# MYO_power_distribution_pcb.net
KiCad netlist of a schematic drawn in EAGLE
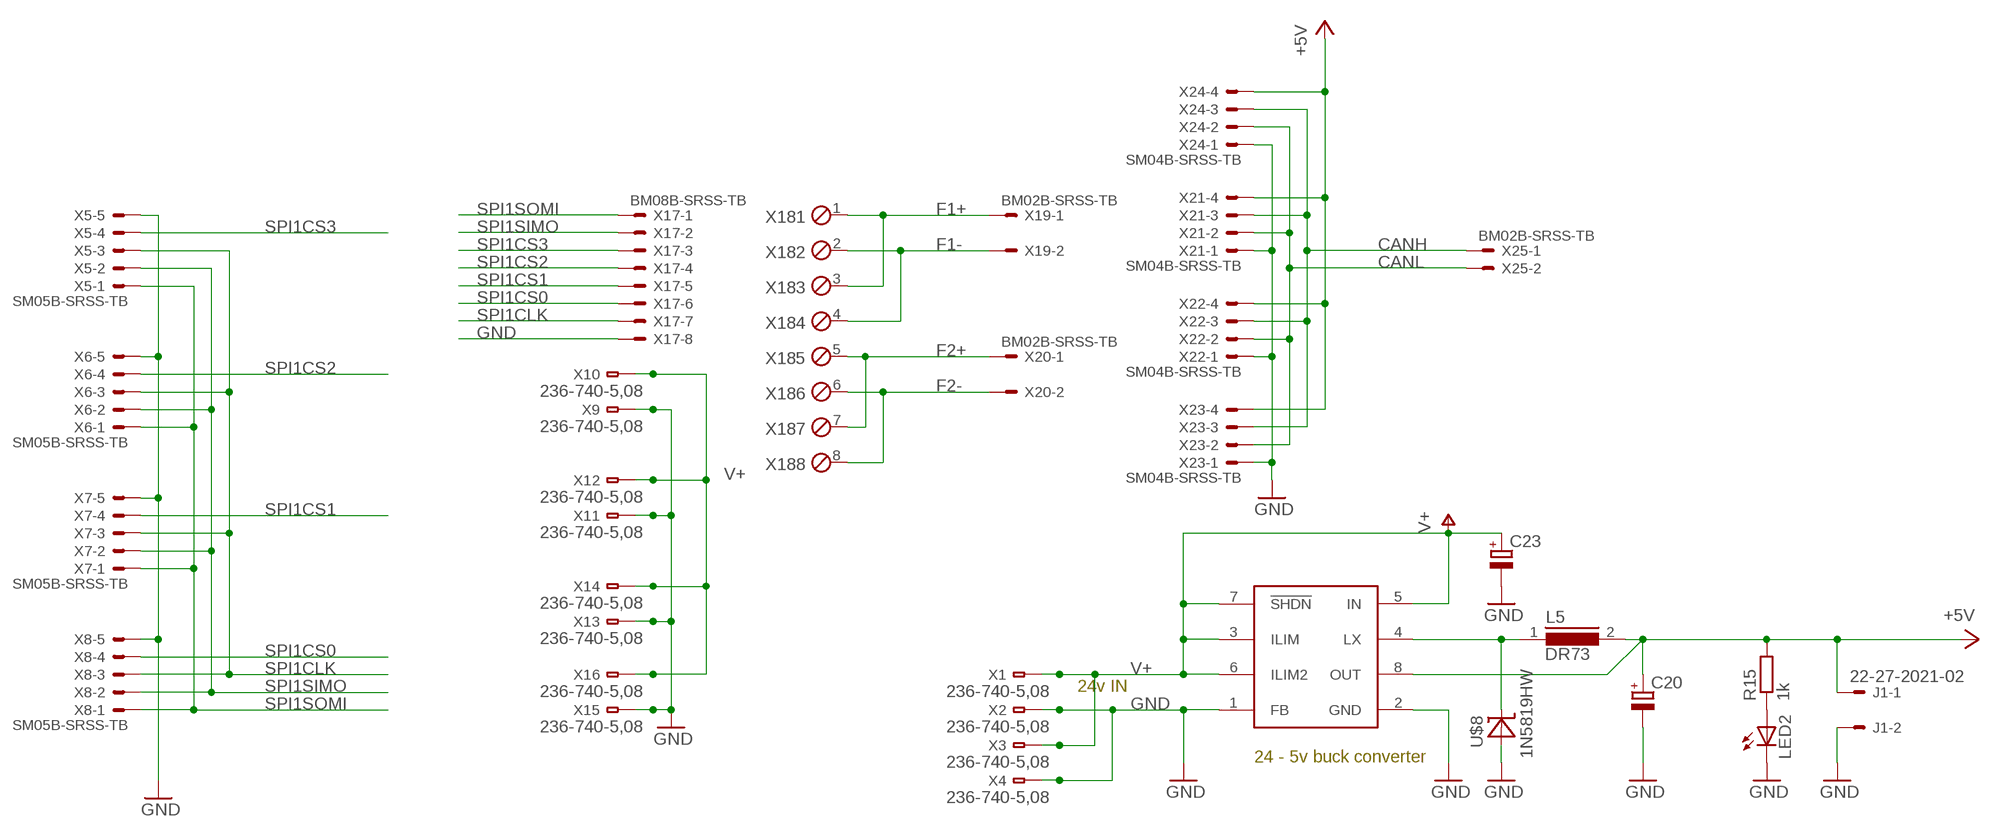
[diagram p0: schematic, sheet 1]

(export (version "E")
  (design (tool "Eeschema 10.0.6"))
  (components
    (comp (ref "C20")
      (value "CPOL-EUC/6032-28R")
      (footprint "eagle-import:C_6032-28R")
      (libsource (lib "eagle-import") (part "CPOL-EUC/6032-28R"))
    )
    (comp (ref "C23")
      (value "CPOL-EUC/6032-28R")
      (footprint "eagle-import:C_6032-28R")
      (libsource (lib "eagle-import") (part "CPOL-EUC/6032-28R"))
    )
    (comp (ref "J1")
      (value "22-27-2021-02")
      (footprint "eagle-import:6410-02")
      (libsource (lib "eagle-import") (part "22-?-0227-2021"))
    )
    (comp (ref "L5")
      (value "DR73")
      (footprint "eagle-import:DR73")
      (libsource (lib "eagle-import") (part "DR73"))
    )
    (comp (ref "LED2")
      (value "LEDCHIP-LED0805")
      (footprint "eagle-import:CHIP-LED0805")
      (libsource (lib "eagle-import") (part "LEDCHIP-LED0805"))
    )
    (comp (ref "R15")
      (value "1k")
      (footprint "eagle-import:R0603")
      (libsource (lib "eagle-import") (part "R-EU_R0603"))
    )
    (comp (ref "U$5")
      (value "MAX1776")
      (footprint "eagle-import:UMAX8")
      (libsource (lib "eagle-import") (part "MAX1776"))
    )
    (comp (ref "U$8")
      (value "1N5819HW")
      (footprint "eagle-import:SOD123")
      (libsource (lib "eagle-import") (part "1N5819HW"))
    )
    (comp (ref "X1")
      (value "236-740-5,08")
      (footprint "eagle-import:236-4XX")
      (libsource (lib "eagle-import") (part "236-5,08-740"))
    )
    (comp (ref "X2")
      (value "236-740-5,08")
      (footprint "eagle-import:236-4XX")
      (libsource (lib "eagle-import") (part "236-5,08-740"))
    )
    (comp (ref "X3")
      (value "236-740-5,08")
      (footprint "eagle-import:236-4XX")
      (libsource (lib "eagle-import") (part "236-5,08-740"))
    )
    (comp (ref "X4")
      (value "236-740-5,08")
      (footprint "eagle-import:236-4XX")
      (libsource (lib "eagle-import") (part "236-5,08-740"))
    )
    (comp (ref "X5")
      (value "SM05B-SRSS-TB")
      (footprint "eagle-import:SM05B-SRSS-TB")
      (libsource (lib "eagle-import") (part "?M05B-SRSS-TBS"))
    )
    (comp (ref "X6")
      (value "SM05B-SRSS-TB")
      (footprint "eagle-import:SM05B-SRSS-TB")
      (libsource (lib "eagle-import") (part "?M05B-SRSS-TBS"))
    )
    (comp (ref "X7")
      (value "SM05B-SRSS-TB")
      (footprint "eagle-import:SM05B-SRSS-TB")
      (libsource (lib "eagle-import") (part "?M05B-SRSS-TBS"))
    )
    (comp (ref "X8")
      (value "SM05B-SRSS-TB")
      (footprint "eagle-import:SM05B-SRSS-TB")
      (libsource (lib "eagle-import") (part "?M05B-SRSS-TBS"))
    )
    (comp (ref "X9")
      (value "236-740-5,08")
      (footprint "eagle-import:236-4XX")
      (libsource (lib "eagle-import") (part "236-5,08-740"))
    )
    (comp (ref "X10")
      (value "236-740-5,08")
      (footprint "eagle-import:236-4XX")
      (libsource (lib "eagle-import") (part "236-5,08-740"))
    )
    (comp (ref "X11")
      (value "236-740-5,08")
      (footprint "eagle-import:236-4XX")
      (libsource (lib "eagle-import") (part "236-5,08-740"))
    )
    (comp (ref "X12")
      (value "236-740-5,08")
      (footprint "eagle-import:236-4XX")
      (libsource (lib "eagle-import") (part "236-5,08-740"))
    )
    (comp (ref "X13")
      (value "236-740-5,08")
      (footprint "eagle-import:236-4XX")
      (libsource (lib "eagle-import") (part "236-5,08-740"))
    )
    (comp (ref "X14")
      (value "236-740-5,08")
      (footprint "eagle-import:236-4XX")
      (libsource (lib "eagle-import") (part "236-5,08-740"))
    )
    (comp (ref "X15")
      (value "236-740-5,08")
      (footprint "eagle-import:236-4XX")
      (libsource (lib "eagle-import") (part "236-5,08-740"))
    )
    (comp (ref "X16")
      (value "236-740-5,08")
      (footprint "eagle-import:236-4XX")
      (libsource (lib "eagle-import") (part "236-5,08-740"))
    )
    (comp (ref "X17")
      (value "BM08B-SRSS-TB")
      (footprint "eagle-import:BM08B-SRSS-TB")
      (libsource (lib "eagle-import") (part "?M08B-SRSS-TBB"))
    )
    (comp (ref "X18")
      (value "CON_PTSA_8")
      (footprint "eagle-import:PHOENIX_PSTA_8")
      (libsource (lib "eagle-import") (part "CON_PTSA_8"))
    )
    (comp (ref "X19")
      (value "BM02B-SRSS-TB")
      (footprint "eagle-import:BM02B-SRSS-TB")
      (libsource (lib "eagle-import") (part "?M02B-SRSS-TBB"))
    )
    (comp (ref "X20")
      (value "BM02B-SRSS-TB")
      (footprint "eagle-import:BM02B-SRSS-TB")
      (libsource (lib "eagle-import") (part "?M02B-SRSS-TBB"))
    )
    (comp (ref "X21")
      (value "SM04B-SRSS-TB")
      (footprint "eagle-import:SM04B-SRSS-TB")
      (libsource (lib "eagle-import") (part "?M04B-SRSS-TBS"))
    )
    (comp (ref "X22")
      (value "SM04B-SRSS-TB")
      (footprint "eagle-import:SM04B-SRSS-TB")
      (libsource (lib "eagle-import") (part "?M04B-SRSS-TBS"))
    )
    (comp (ref "X23")
      (value "SM04B-SRSS-TB")
      (footprint "eagle-import:SM04B-SRSS-TB")
      (libsource (lib "eagle-import") (part "?M04B-SRSS-TBS"))
    )
    (comp (ref "X24")
      (value "SM04B-SRSS-TB")
      (footprint "eagle-import:SM04B-SRSS-TB")
      (libsource (lib "eagle-import") (part "?M04B-SRSS-TBS"))
    )
    (comp (ref "X25")
      (value "BM02B-SRSS-TB")
      (footprint "eagle-import:BM02B-SRSS-TB")
      (libsource (lib "eagle-import") (part "?M02B-SRSS-TBB"))
    )
  )
  (nets
    (net (code "1") (name "+5V") (class "Default")
      (node (ref "C20") (pin "+") (pinfunction "+_+") (pintype "passive"))
      (node (ref "J1") (pin "1") (pinfunction "S_1") (pintype "passive"))
      (node (ref "L5") (pin "2") (pinfunction "2_2") (pintype "passive"))
      (node (ref "R15") (pin "2") (pinfunction "2_2") (pintype "passive"))
      (node (ref "U$5") (pin "8") (pinfunction "OUT_8") (pintype "bidirectional"))
      (node (ref "X21") (pin "4") (pinfunction "S_4") (pintype "passive"))
      (node (ref "X22") (pin "4") (pinfunction "S_4") (pintype "passive"))
      (node (ref "X23") (pin "4") (pinfunction "S_4") (pintype "passive"))
      (node (ref "X24") (pin "4") (pinfunction "S_4") (pintype "passive"))
    )
    (net (code "2") (name "/CANH") (class "Default")
      (node (ref "X21") (pin "3") (pinfunction "S_3") (pintype "passive"))
      (node (ref "X22") (pin "3") (pinfunction "S_3") (pintype "passive"))
      (node (ref "X23") (pin "3") (pinfunction "S_3") (pintype "passive"))
      (node (ref "X24") (pin "3") (pinfunction "S_3") (pintype "passive"))
      (node (ref "X25") (pin "1") (pinfunction "S_1") (pintype "passive"))
    )
    (net (code "3") (name "/CANL") (class "Default")
      (node (ref "X21") (pin "2") (pinfunction "S_2") (pintype "passive"))
      (node (ref "X22") (pin "2") (pinfunction "S_2") (pintype "passive"))
      (node (ref "X23") (pin "2") (pinfunction "S_2") (pintype "passive"))
      (node (ref "X24") (pin "2") (pinfunction "S_2") (pintype "passive"))
      (node (ref "X25") (pin "2") (pinfunction "S_2") (pintype "passive"))
    )
    (net (code "4") (name "/F1+") (class "Default")
      (node (ref "X18") (pin "1") (pinfunction "1_1") (pintype "passive"))
      (node (ref "X18") (pin "3") (pinfunction "1_3") (pintype "passive"))
      (node (ref "X19") (pin "1") (pinfunction "S_1") (pintype "passive"))
    )
    (net (code "5") (name "/F1-") (class "Default")
      (node (ref "X18") (pin "2") (pinfunction "1_2") (pintype "passive"))
      (node (ref "X18") (pin "4") (pinfunction "1_4") (pintype "passive"))
      (node (ref "X19") (pin "2") (pinfunction "S_2") (pintype "passive"))
    )
    (net (code "6") (name "/F2+") (class "Default")
      (node (ref "X18") (pin "5") (pinfunction "1_5") (pintype "passive"))
      (node (ref "X18") (pin "7") (pinfunction "1_7") (pintype "passive"))
      (node (ref "X20") (pin "1") (pinfunction "S_1") (pintype "passive"))
    )
    (net (code "7") (name "/F2-") (class "Default")
      (node (ref "X18") (pin "6") (pinfunction "1_6") (pintype "passive"))
      (node (ref "X18") (pin "8") (pinfunction "1_8") (pintype "passive"))
      (node (ref "X20") (pin "2") (pinfunction "S_2") (pintype "passive"))
    )
    (net (code "8") (name "/SPI1CLK") (class "Default")
      (node (ref "X17") (pin "7") (pinfunction "S_7") (pintype "passive"))
      (node (ref "X5") (pin "3") (pinfunction "S_3") (pintype "passive"))
      (node (ref "X6") (pin "3") (pinfunction "S_3") (pintype "passive"))
      (node (ref "X7") (pin "3") (pinfunction "S_3") (pintype "passive"))
      (node (ref "X8") (pin "3") (pinfunction "S_3") (pintype "passive"))
    )
    (net (code "9") (name "/SPI1CS0") (class "Default")
      (node (ref "X17") (pin "6") (pinfunction "S_6") (pintype "passive"))
      (node (ref "X8") (pin "4") (pinfunction "S_4") (pintype "passive"))
    )
    (net (code "10") (name "/SPI1CS1") (class "Default")
      (node (ref "X17") (pin "5") (pinfunction "S_5") (pintype "passive"))
      (node (ref "X7") (pin "4") (pinfunction "S_4") (pintype "passive"))
    )
    (net (code "11") (name "/SPI1CS2") (class "Default")
      (node (ref "X17") (pin "4") (pinfunction "S_4") (pintype "passive"))
      (node (ref "X6") (pin "4") (pinfunction "S_4") (pintype "passive"))
    )
    (net (code "12") (name "/SPI1CS3") (class "Default")
      (node (ref "X17") (pin "3") (pinfunction "S_3") (pintype "passive"))
      (node (ref "X5") (pin "4") (pinfunction "S_4") (pintype "passive"))
    )
    (net (code "13") (name "/SPI1SIMO") (class "Default")
      (node (ref "X17") (pin "2") (pinfunction "S_2") (pintype "passive"))
      (node (ref "X5") (pin "2") (pinfunction "S_2") (pintype "passive"))
      (node (ref "X6") (pin "2") (pinfunction "S_2") (pintype "passive"))
      (node (ref "X7") (pin "2") (pinfunction "S_2") (pintype "passive"))
      (node (ref "X8") (pin "2") (pinfunction "S_2") (pintype "passive"))
    )
    (net (code "14") (name "/SPI1SOMI") (class "Default")
      (node (ref "X17") (pin "1") (pinfunction "S_1") (pintype "passive"))
      (node (ref "X5") (pin "1") (pinfunction "S_1") (pintype "passive"))
      (node (ref "X6") (pin "1") (pinfunction "S_1") (pintype "passive"))
      (node (ref "X7") (pin "1") (pinfunction "S_1") (pintype "passive"))
      (node (ref "X8") (pin "1") (pinfunction "S_1") (pintype "passive"))
    )
    (net (code "15") (name "GND") (class "Default")
      (node (ref "C20") (pin "-") (pinfunction "-_-") (pintype "passive"))
      (node (ref "C23") (pin "-") (pinfunction "-_-") (pintype "passive"))
      (node (ref "J1") (pin "2") (pinfunction "S_2") (pintype "passive"))
      (node (ref "LED2") (pin "C") (pinfunction "C_C") (pintype "passive"))
      (node (ref "U$5") (pin "1") (pinfunction "FB_1") (pintype "bidirectional"))
      (node (ref "U$5") (pin "2") (pinfunction "GND_2") (pintype "bidirectional"))
      (node (ref "U$8") (pin "A") (pinfunction "A_A") (pintype "passive"))
      (node (ref "X11") (pin "1@1") (pinfunction "A1_1@1") (pintype "passive"))
      (node (ref "X11") (pin "1@2") (pinfunction "B1_1@2") (pintype "passive"))
      (node (ref "X13") (pin "1@1") (pinfunction "A1_1@1") (pintype "passive"))
      (node (ref "X13") (pin "1@2") (pinfunction "B1_1@2") (pintype "passive"))
      (node (ref "X15") (pin "1@1") (pinfunction "A1_1@1") (pintype "passive"))
      (node (ref "X15") (pin "1@2") (pinfunction "B1_1@2") (pintype "passive"))
      (node (ref "X17") (pin "8") (pinfunction "S_8") (pintype "passive"))
      (node (ref "X2") (pin "1@1") (pinfunction "A1_1@1") (pintype "passive"))
      (node (ref "X2") (pin "1@2") (pinfunction "B1_1@2") (pintype "passive"))
      (node (ref "X21") (pin "1") (pinfunction "S_1") (pintype "passive"))
      (node (ref "X22") (pin "1") (pinfunction "S_1") (pintype "passive"))
      (node (ref "X23") (pin "1") (pinfunction "S_1") (pintype "passive"))
      (node (ref "X24") (pin "1") (pinfunction "S_1") (pintype "passive"))
      (node (ref "X4") (pin "1@1") (pinfunction "A1_1@1") (pintype "passive"))
      (node (ref "X4") (pin "1@2") (pinfunction "B1_1@2") (pintype "passive"))
      (node (ref "X5") (pin "5") (pinfunction "S_5") (pintype "passive"))
      (node (ref "X6") (pin "5") (pinfunction "S_5") (pintype "passive"))
      (node (ref "X7") (pin "5") (pinfunction "S_5") (pintype "passive"))
      (node (ref "X8") (pin "5") (pinfunction "S_5") (pintype "passive"))
      (node (ref "X9") (pin "1@1") (pinfunction "A1_1@1") (pintype "passive"))
      (node (ref "X9") (pin "1@2") (pinfunction "B1_1@2") (pintype "passive"))
    )
    (net (code "16") (name "Net-(LED2-PadA)") (class "Default")
      (node (ref "LED2") (pin "A") (pinfunction "A_A") (pintype "passive"))
      (node (ref "R15") (pin "1") (pinfunction "1_1") (pintype "passive"))
    )
    (net (code "17") (name "Net-(U$5-LX)") (class "Default")
      (node (ref "L5") (pin "1") (pinfunction "1_1") (pintype "passive"))
      (node (ref "U$5") (pin "4") (pinfunction "LX_4") (pintype "bidirectional"))
      (node (ref "U$8") (pin "C") (pinfunction "C_C") (pintype "passive"))
    )
    (net (code "18") (name "V+") (class "Default")
      (node (ref "C23") (pin "+") (pinfunction "+_+") (pintype "passive"))
      (node (ref "U$5") (pin "3") (pinfunction "ILIM_3") (pintype "bidirectional"))
      (node (ref "U$5") (pin "5") (pinfunction "IN_5") (pintype "bidirectional"))
      (node (ref "U$5") (pin "6") (pinfunction "ILIM2_6") (pintype "bidirectional"))
      (node (ref "U$5") (pin "7") (pinfunction "~{SHDN}_7") (pintype "bidirectional"))
      (node (ref "X1") (pin "1@1") (pinfunction "A1_1@1") (pintype "passive"))
      (node (ref "X1") (pin "1@2") (pinfunction "B1_1@2") (pintype "passive"))
      (node (ref "X10") (pin "1@1") (pinfunction "A1_1@1") (pintype "passive"))
      (node (ref "X10") (pin "1@2") (pinfunction "B1_1@2") (pintype "passive"))
      (node (ref "X12") (pin "1@1") (pinfunction "A1_1@1") (pintype "passive"))
      (node (ref "X12") (pin "1@2") (pinfunction "B1_1@2") (pintype "passive"))
      (node (ref "X14") (pin "1@1") (pinfunction "A1_1@1") (pintype "passive"))
      (node (ref "X14") (pin "1@2") (pinfunction "B1_1@2") (pintype "passive"))
      (node (ref "X16") (pin "1@1") (pinfunction "A1_1@1") (pintype "passive"))
      (node (ref "X16") (pin "1@2") (pinfunction "B1_1@2") (pintype "passive"))
      (node (ref "X3") (pin "1@1") (pinfunction "A1_1@1") (pintype "passive"))
      (node (ref "X3") (pin "1@2") (pinfunction "B1_1@2") (pintype "passive"))
    )
  )
)
